# Sheet1.net
KiCad netlist of a schematic drawn in Altium Designer
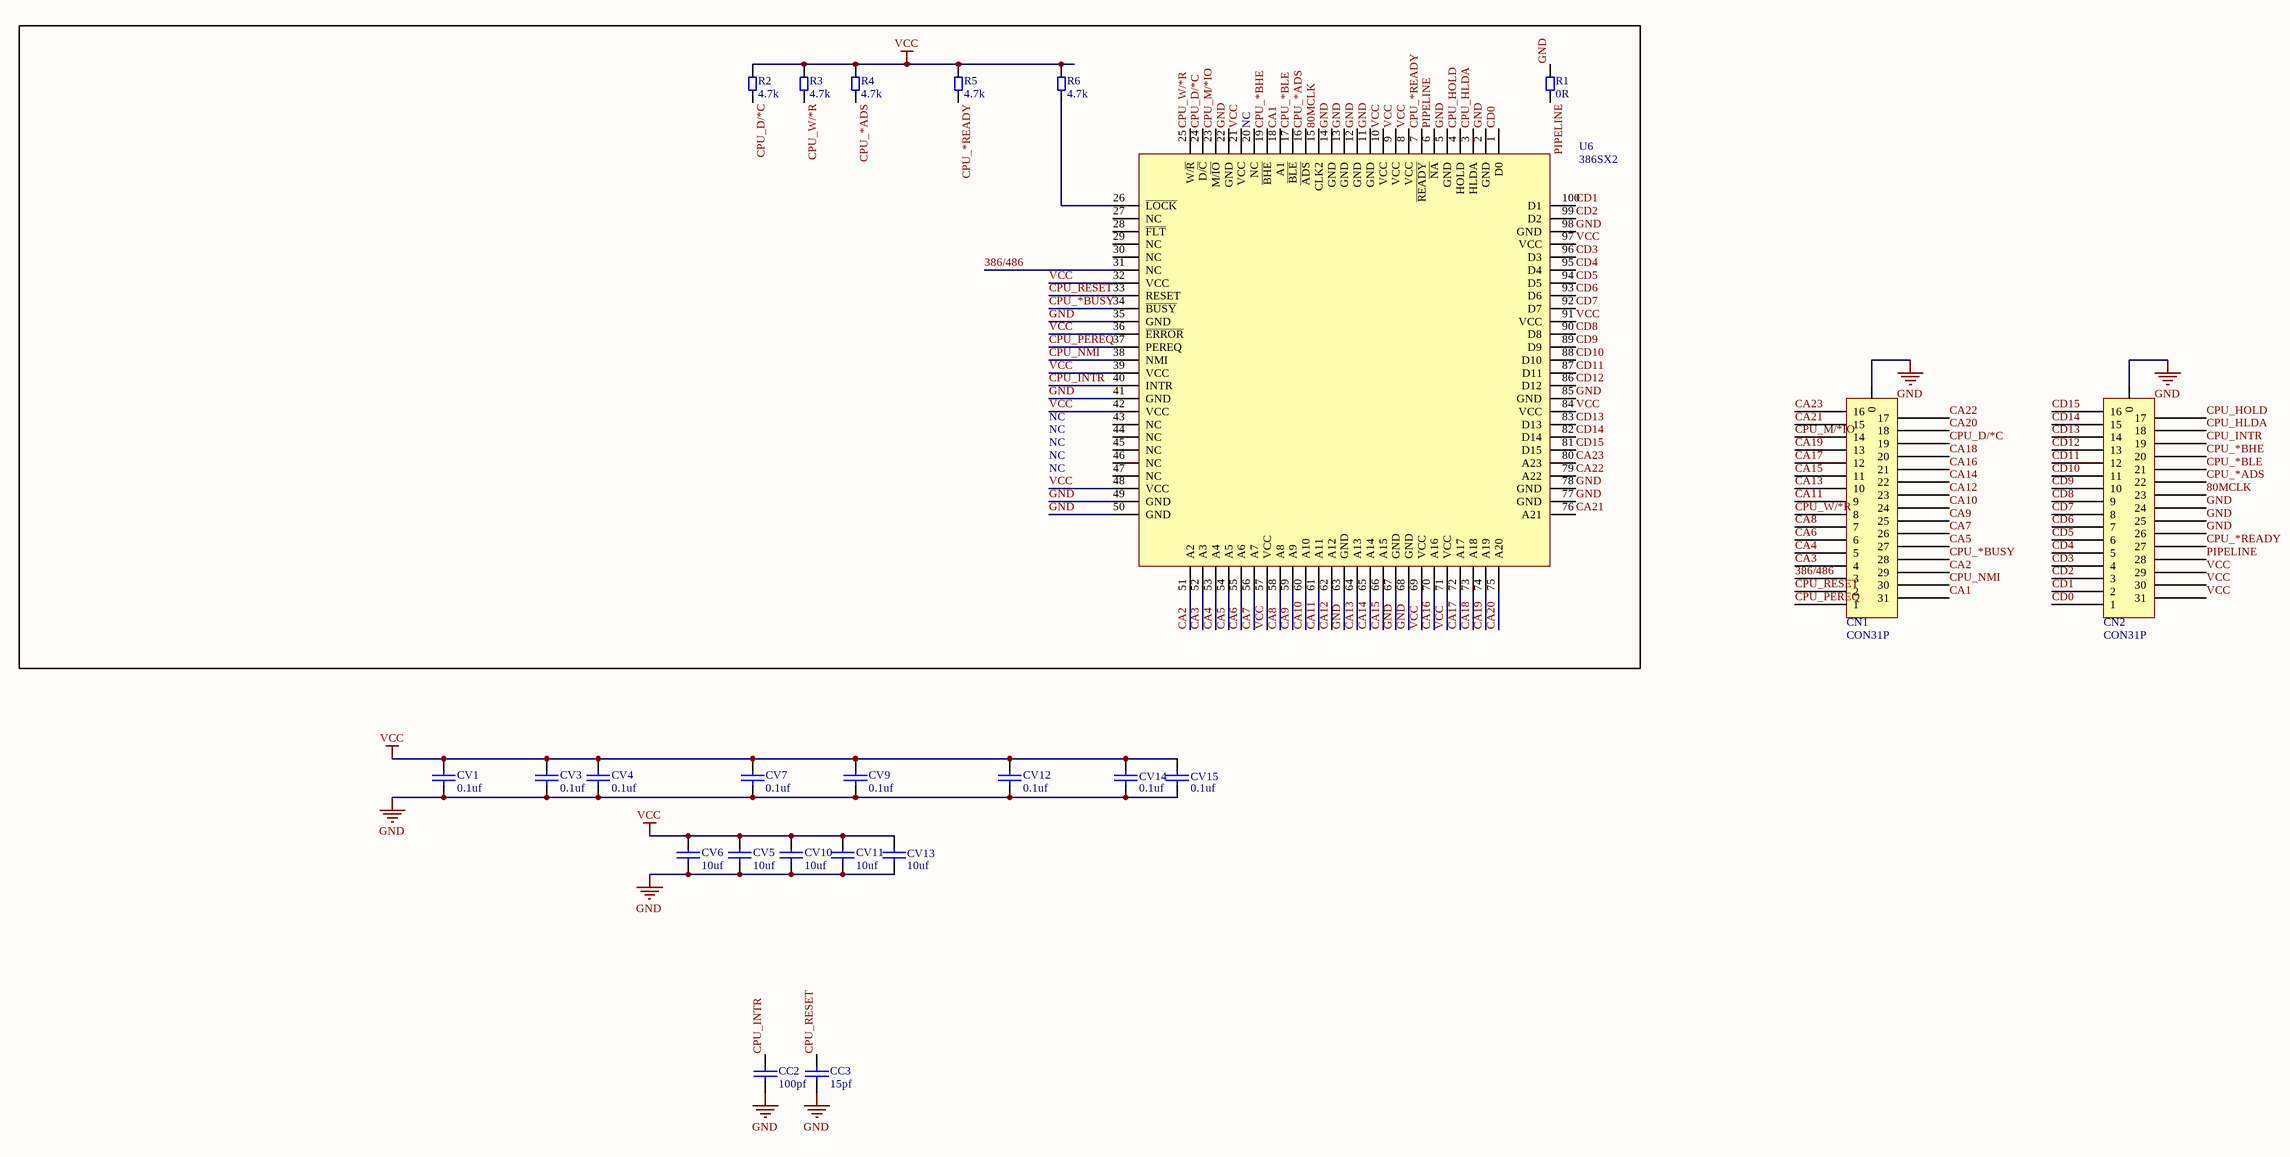
[diagram p0: Sheet1.SchDoc]

(export (version "E")
  (design (tool "Eeschema 10.0.6"))
  (components
    (comp (ref "CC2") (value "100pf") (footprint "C0603") (libsource (lib "电阻电容二极管") (part "CAP")))
    (comp (ref "CC3") (value "15pf") (footprint "C0603") (libsource (lib "电阻电容二极管") (part "CAP")))
    (comp (ref "CN1") (value "CON31P") (footprint "BTB1.0-31P-B") (libsource (lib "常用元件库") (part "CON31P")))
    (comp (ref "CN2") (value "CON31P") (footprint "BTB1.0-31P-B") (libsource (lib "常用元件库") (part "CON31P")))
    (comp (ref "CV1") (value "0.1uf") (footprint "C0603") (libsource (lib "电阻电容二极管") (part "CAP")))
    (comp (ref "CV3") (value "0.1uf") (footprint "C0603") (libsource (lib "电阻电容二极管") (part "CAP")))
    (comp (ref "CV4") (value "0.1uf") (footprint "C0603") (libsource (lib "电阻电容二极管") (part "CAP")))
    (comp (ref "CV5") (value "10uf") (footprint "C0603") (libsource (lib "电阻电容二极管") (part "CAP")))
    (comp (ref "CV6") (value "10uf") (footprint "C0603") (libsource (lib "电阻电容二极管") (part "CAP")))
    (comp (ref "CV7") (value "0.1uf") (footprint "C0603") (libsource (lib "电阻电容二极管") (part "CAP")))
    (comp (ref "CV9") (value "0.1uf") (footprint "C0603") (libsource (lib "电阻电容二极管") (part "CAP")))
    (comp (ref "CV10") (value "10uf") (footprint "C0603") (libsource (lib "电阻电容二极管") (part "CAP")))
    (comp (ref "CV11") (value "10uf") (footprint "C0603") (libsource (lib "电阻电容二极管") (part "CAP")))
    (comp (ref "CV12") (value "0.1uf") (footprint "C0603") (libsource (lib "电阻电容二极管") (part "CAP")))
    (comp (ref "CV13") (value "10uf") (footprint "C0603") (libsource (lib "电阻电容二极管") (part "CAP")))
    (comp (ref "CV14") (value "0.1uf") (footprint "C0603") (libsource (lib "电阻电容二极管") (part "CAP")))
    (comp (ref "CV15") (value "0.1uf") (footprint "C0603") (libsource (lib "电阻电容二极管") (part "CAP")))
    (comp (ref "R1") (value "0R") (footprint "R0603") (libsource (lib "电阻电容二极管") (part "RES2")))
    (comp (ref "R2") (value "4.7k") (footprint "R0603") (libsource (lib "电阻电容二极管") (part "RES2")))
    (comp (ref "R3") (value "4.7k") (footprint "R0603") (libsource (lib "电阻电容二极管") (part "RES2")))
    (comp (ref "R4") (value "4.7k") (footprint "R0603") (libsource (lib "电阻电容二极管") (part "RES2")))
    (comp (ref "R5") (value "4.7k") (footprint "R0603") (libsource (lib "电阻电容二极管") (part "RES2")))
    (comp (ref "R6") (value "4.7k") (footprint "R0603") (libsource (lib "电阻电容二极管") (part "RES2")))
    (comp (ref "U6") (value "386SX2") (footprint "PQFP100A") (libsource (lib "微机原理") (part "386SX2")))
  )
  (nets
    (net (code "1") (name "/80MCLK") (class "Default")
      (node (ref "CN2") (pin "23") (pinfunction "23_23") (pintype "passive"))
      (node (ref "U6") (pin "15") (pinfunction "CLK2_15") (pintype "passive"))
    )
    (net (code "2") (name "/386{slash}486") (class "Default")
      (node (ref "CN1") (pin "3") (pinfunction "3_3") (pintype "passive"))
      (node (ref "U6") (pin "31") (pinfunction "NC_31") (pintype "passive"))
    )
    (net (code "3") (name "/CA1") (class "Default")
      (node (ref "CN1") (pin "31") (pinfunction "31_31") (pintype "passive"))
      (node (ref "U6") (pin "18") (pinfunction "A1_18") (pintype "passive"))
    )
    (net (code "4") (name "/CA2") (class "Default")
      (node (ref "CN1") (pin "29") (pinfunction "29_29") (pintype "passive"))
      (node (ref "U6") (pin "51") (pinfunction "A2_51") (pintype "passive"))
    )
    (net (code "5") (name "/CA3") (class "Default")
      (node (ref "CN1") (pin "4") (pinfunction "4_4") (pintype "passive"))
      (node (ref "U6") (pin "52") (pinfunction "A3_52") (pintype "passive"))
    )
    (net (code "6") (name "/CA4") (class "Default")
      (node (ref "CN1") (pin "5") (pinfunction "5_5") (pintype "passive"))
      (node (ref "U6") (pin "53") (pinfunction "A4_53") (pintype "passive"))
    )
    (net (code "7") (name "/CA5") (class "Default")
      (node (ref "CN1") (pin "27") (pinfunction "27_27") (pintype "passive"))
      (node (ref "U6") (pin "54") (pinfunction "A5_54") (pintype "passive"))
    )
    (net (code "8") (name "/CA6") (class "Default")
      (node (ref "CN1") (pin "6") (pinfunction "6_6") (pintype "passive"))
      (node (ref "U6") (pin "55") (pinfunction "A6_55") (pintype "passive"))
    )
    (net (code "9") (name "/CA7") (class "Default")
      (node (ref "CN1") (pin "26") (pinfunction "26_26") (pintype "passive"))
      (node (ref "U6") (pin "56") (pinfunction "A7_56") (pintype "passive"))
    )
    (net (code "10") (name "/CA8") (class "Default")
      (node (ref "CN1") (pin "7") (pinfunction "7_7") (pintype "passive"))
      (node (ref "U6") (pin "58") (pinfunction "A8_58") (pintype "passive"))
    )
    (net (code "11") (name "/CA9") (class "Default")
      (node (ref "CN1") (pin "25") (pinfunction "25_25") (pintype "passive"))
      (node (ref "U6") (pin "59") (pinfunction "A9_59") (pintype "passive"))
    )
    (net (code "12") (name "/CA10") (class "Default")
      (node (ref "CN1") (pin "24") (pinfunction "24_24") (pintype "passive"))
      (node (ref "U6") (pin "60") (pinfunction "A10_60") (pintype "passive"))
    )
    (net (code "13") (name "/CA11") (class "Default")
      (node (ref "CN1") (pin "9") (pinfunction "9_9") (pintype "passive"))
      (node (ref "U6") (pin "61") (pinfunction "A11_61") (pintype "passive"))
    )
    (net (code "14") (name "/CA12") (class "Default")
      (node (ref "CN1") (pin "23") (pinfunction "23_23") (pintype "passive"))
      (node (ref "U6") (pin "62") (pinfunction "A12_62") (pintype "passive"))
    )
    (net (code "15") (name "/CA13") (class "Default")
      (node (ref "CN1") (pin "10") (pinfunction "10_10") (pintype "passive"))
      (node (ref "U6") (pin "64") (pinfunction "A13_64") (pintype "passive"))
    )
    (net (code "16") (name "/CA14") (class "Default")
      (node (ref "CN1") (pin "22") (pinfunction "22_22") (pintype "passive"))
      (node (ref "U6") (pin "65") (pinfunction "A14_65") (pintype "passive"))
    )
    (net (code "17") (name "/CA15") (class "Default")
      (node (ref "CN1") (pin "11") (pinfunction "11_11") (pintype "passive"))
      (node (ref "U6") (pin "66") (pinfunction "A15_66") (pintype "passive"))
    )
    (net (code "18") (name "/CA16") (class "Default")
      (node (ref "CN1") (pin "21") (pinfunction "21_21") (pintype "passive"))
      (node (ref "U6") (pin "70") (pinfunction "A16_70") (pintype "passive"))
    )
    (net (code "19") (name "/CA17") (class "Default")
      (node (ref "CN1") (pin "12") (pinfunction "12_12") (pintype "passive"))
      (node (ref "U6") (pin "72") (pinfunction "A17_72") (pintype "passive"))
    )
    (net (code "20") (name "/CA18") (class "Default")
      (node (ref "CN1") (pin "20") (pinfunction "20_20") (pintype "passive"))
      (node (ref "U6") (pin "73") (pinfunction "A18_73") (pintype "passive"))
    )
    (net (code "21") (name "/CA19") (class "Default")
      (node (ref "CN1") (pin "13") (pinfunction "13_13") (pintype "passive"))
      (node (ref "U6") (pin "74") (pinfunction "A19_74") (pintype "passive"))
    )
    (net (code "22") (name "/CA20") (class "Default")
      (node (ref "CN1") (pin "18") (pinfunction "18_18") (pintype "passive"))
      (node (ref "U6") (pin "75") (pinfunction "A20_75") (pintype "passive"))
    )
    (net (code "23") (name "/CA21") (class "Default")
      (node (ref "CN1") (pin "15") (pinfunction "15_15") (pintype "passive"))
      (node (ref "U6") (pin "76") (pinfunction "A21_76") (pintype "passive"))
    )
    (net (code "24") (name "/CA22") (class "Default")
      (node (ref "CN1") (pin "17") (pinfunction "17_17") (pintype "passive"))
      (node (ref "U6") (pin "79") (pinfunction "A22_79") (pintype "passive"))
    )
    (net (code "25") (name "/CA23") (class "Default")
      (node (ref "CN1") (pin "16") (pinfunction "16_16") (pintype "passive"))
      (node (ref "U6") (pin "80") (pinfunction "A23_80") (pintype "passive"))
    )
    (net (code "26") (name "/CD0") (class "Default")
      (node (ref "CN2") (pin "1") (pinfunction "1_1") (pintype "passive"))
      (node (ref "U6") (pin "1") (pinfunction "D0_1") (pintype "passive"))
    )
    (net (code "27") (name "/CD1") (class "Default")
      (node (ref "CN2") (pin "2") (pinfunction "2_2") (pintype "passive"))
      (node (ref "U6") (pin "100") (pinfunction "D1_100") (pintype "passive"))
    )
    (net (code "28") (name "/CD2") (class "Default")
      (node (ref "CN2") (pin "3") (pinfunction "3_3") (pintype "passive"))
      (node (ref "U6") (pin "99") (pinfunction "D2_99") (pintype "passive"))
    )
    (net (code "29") (name "/CD3") (class "Default")
      (node (ref "CN2") (pin "4") (pinfunction "4_4") (pintype "passive"))
      (node (ref "U6") (pin "96") (pinfunction "D3_96") (pintype "passive"))
    )
    (net (code "30") (name "/CD4") (class "Default")
      (node (ref "CN2") (pin "5") (pinfunction "5_5") (pintype "passive"))
      (node (ref "U6") (pin "95") (pinfunction "D4_95") (pintype "passive"))
    )
    (net (code "31") (name "/CD5") (class "Default")
      (node (ref "CN2") (pin "6") (pinfunction "6_6") (pintype "passive"))
      (node (ref "U6") (pin "94") (pinfunction "D5_94") (pintype "passive"))
    )
    (net (code "32") (name "/CD6") (class "Default")
      (node (ref "CN2") (pin "7") (pinfunction "7_7") (pintype "passive"))
      (node (ref "U6") (pin "93") (pinfunction "D6_93") (pintype "passive"))
    )
    (net (code "33") (name "/CD7") (class "Default")
      (node (ref "CN2") (pin "8") (pinfunction "8_8") (pintype "passive"))
      (node (ref "U6") (pin "92") (pinfunction "D7_92") (pintype "passive"))
    )
    (net (code "34") (name "/CD8") (class "Default")
      (node (ref "CN2") (pin "9") (pinfunction "9_9") (pintype "passive"))
      (node (ref "U6") (pin "90") (pinfunction "D8_90") (pintype "passive"))
    )
    (net (code "35") (name "/CD9") (class "Default")
      (node (ref "CN2") (pin "10") (pinfunction "10_10") (pintype "passive"))
      (node (ref "U6") (pin "89") (pinfunction "D9_89") (pintype "passive"))
    )
    (net (code "36") (name "/CD10") (class "Default")
      (node (ref "CN2") (pin "11") (pinfunction "11_11") (pintype "passive"))
      (node (ref "U6") (pin "88") (pinfunction "D10_88") (pintype "passive"))
    )
    (net (code "37") (name "/CD11") (class "Default")
      (node (ref "CN2") (pin "12") (pinfunction "12_12") (pintype "passive"))
      (node (ref "U6") (pin "87") (pinfunction "D11_87") (pintype "passive"))
    )
    (net (code "38") (name "/CD12") (class "Default")
      (node (ref "CN2") (pin "13") (pinfunction "13_13") (pintype "passive"))
      (node (ref "U6") (pin "86") (pinfunction "D12_86") (pintype "passive"))
    )
    (net (code "39") (name "/CD13") (class "Default")
      (node (ref "CN2") (pin "14") (pinfunction "14_14") (pintype "passive"))
      (node (ref "U6") (pin "83") (pinfunction "D13_83") (pintype "passive"))
    )
    (net (code "40") (name "/CD14") (class "Default")
      (node (ref "CN2") (pin "15") (pinfunction "15_15") (pintype "passive"))
      (node (ref "U6") (pin "82") (pinfunction "D14_82") (pintype "passive"))
    )
    (net (code "41") (name "/CD15") (class "Default")
      (node (ref "CN2") (pin "16") (pinfunction "16_16") (pintype "passive"))
      (node (ref "U6") (pin "81") (pinfunction "D15_81") (pintype "passive"))
    )
    (net (code "42") (name "/CPU_*ADS") (class "Default")
      (node (ref "CN2") (pin "22") (pinfunction "22_22") (pintype "passive"))
      (node (ref "R4") (pin "1") (pinfunction "1_1") (pintype "passive"))
      (node (ref "U6") (pin "16") (pinfunction "~{ADS}_16") (pintype "passive"))
    )
    (net (code "43") (name "/CPU_*BHE") (class "Default")
      (node (ref "CN2") (pin "20") (pinfunction "20_20") (pintype "passive"))
      (node (ref "U6") (pin "19") (pinfunction "~{BHE}_19") (pintype "passive"))
    )
    (net (code "44") (name "/CPU_*BLE") (class "Default")
      (node (ref "CN2") (pin "21") (pinfunction "21_21") (pintype "passive"))
      (node (ref "U6") (pin "17") (pinfunction "~{BLE}_17") (pintype "passive"))
    )
    (net (code "45") (name "/CPU_*BUSY") (class "Default")
      (node (ref "CN1") (pin "28") (pinfunction "28_28") (pintype "passive"))
      (node (ref "U6") (pin "34") (pinfunction "~{BUSY}_34") (pintype "passive"))
    )
    (net (code "46") (name "/CPU_*READY") (class "Default")
      (node (ref "CN2") (pin "27") (pinfunction "27_27") (pintype "passive"))
      (node (ref "R5") (pin "1") (pinfunction "1_1") (pintype "passive"))
      (node (ref "U6") (pin "7") (pinfunction "~{READY}_7") (pintype "passive"))
    )
    (net (code "47") (name "/CPU_D{slash}*C") (class "Default")
      (node (ref "CN1") (pin "19") (pinfunction "19_19") (pintype "passive"))
      (node (ref "R2") (pin "1") (pinfunction "1_1") (pintype "passive"))
      (node (ref "U6") (pin "24") (pinfunction "D/~{C}_24") (pintype "passive"))
    )
    (net (code "48") (name "/CPU_HLDA") (class "Default")
      (node (ref "CN2") (pin "18") (pinfunction "18_18") (pintype "passive"))
      (node (ref "U6") (pin "3") (pinfunction "HLDA_3") (pintype "passive"))
    )
    (net (code "49") (name "/CPU_HOLD") (class "Default")
      (node (ref "CN2") (pin "17") (pinfunction "17_17") (pintype "passive"))
      (node (ref "U6") (pin "4") (pinfunction "HOLD_4") (pintype "passive"))
    )
    (net (code "50") (name "/CPU_INTR") (class "Default")
      (node (ref "CC2") (pin "1") (pinfunction "1_1") (pintype "passive"))
      (node (ref "CN2") (pin "19") (pinfunction "19_19") (pintype "passive"))
      (node (ref "U6") (pin "40") (pinfunction "INTR_40") (pintype "passive"))
    )
    (net (code "51") (name "/CPU_M{slash}*IO") (class "Default")
      (node (ref "CN1") (pin "14") (pinfunction "14_14") (pintype "passive"))
      (node (ref "U6") (pin "23") (pinfunction "M/~{IO}_23") (pintype "passive"))
    )
    (net (code "52") (name "/CPU_NMI") (class "Default")
      (node (ref "CN1") (pin "30") (pinfunction "30_30") (pintype "passive"))
      (node (ref "U6") (pin "38") (pinfunction "NMI_38") (pintype "passive"))
    )
    (net (code "53") (name "/CPU_PEREQ") (class "Default")
      (node (ref "CN1") (pin "1") (pinfunction "1_1") (pintype "passive"))
      (node (ref "U6") (pin "37") (pinfunction "PEREQ_37") (pintype "passive"))
    )
    (net (code "54") (name "/CPU_RESET") (class "Default")
      (node (ref "CC3") (pin "1") (pinfunction "1_1") (pintype "passive"))
      (node (ref "CN1") (pin "2") (pinfunction "2_2") (pintype "passive"))
      (node (ref "U6") (pin "33") (pinfunction "RESET_33") (pintype "passive"))
    )
    (net (code "55") (name "/CPU_W{slash}*R") (class "Default")
      (node (ref "CN1") (pin "8") (pinfunction "8_8") (pintype "passive"))
      (node (ref "R3") (pin "1") (pinfunction "1_1") (pintype "passive"))
      (node (ref "U6") (pin "25") (pinfunction "W/~{R}_25") (pintype "passive"))
    )
    (net (code "56") (name "/PIPELINE") (class "Default")
      (node (ref "CN2") (pin "28") (pinfunction "28_28") (pintype "passive"))
      (node (ref "R1") (pin "1") (pinfunction "1_1") (pintype "passive"))
      (node (ref "U6") (pin "6") (pinfunction "~{NA}_6") (pintype "passive"))
    )
    (net (code "57") (name "GND") (class "Default")
      (node (ref "CC2") (pin "2") (pinfunction "2_2") (pintype "passive"))
      (node (ref "CC3") (pin "2") (pinfunction "2_2") (pintype "passive"))
      (node (ref "CN1") (pin "0") (pinfunction "0_0") (pintype "passive"))
      (node (ref "CN2") (pin "0") (pinfunction "0_0") (pintype "passive"))
      (node (ref "CN2") (pin "24") (pinfunction "24_24") (pintype "passive"))
      (node (ref "CN2") (pin "25") (pinfunction "25_25") (pintype "passive"))
      (node (ref "CN2") (pin "26") (pinfunction "26_26") (pintype "passive"))
      (node (ref "CV1") (pin "2") (pinfunction "2_2") (pintype "passive"))
      (node (ref "CV10") (pin "2") (pinfunction "2_2") (pintype "passive"))
      (node (ref "CV11") (pin "2") (pinfunction "2_2") (pintype "passive"))
      (node (ref "CV12") (pin "2") (pinfunction "2_2") (pintype "passive"))
      (node (ref "CV13") (pin "2") (pinfunction "2_2") (pintype "passive"))
      (node (ref "CV14") (pin "2") (pinfunction "2_2") (pintype "passive"))
      (node (ref "CV15") (pin "2") (pinfunction "2_2") (pintype "passive"))
      (node (ref "CV3") (pin "2") (pinfunction "2_2") (pintype "passive"))
      (node (ref "CV4") (pin "2") (pinfunction "2_2") (pintype "passive"))
      (node (ref "CV5") (pin "2") (pinfunction "2_2") (pintype "passive"))
      (node (ref "CV6") (pin "2") (pinfunction "2_2") (pintype "passive"))
      (node (ref "CV7") (pin "2") (pinfunction "2_2") (pintype "passive"))
      (node (ref "CV9") (pin "2") (pinfunction "2_2") (pintype "passive"))
      (node (ref "R1") (pin "2") (pinfunction "2_2") (pintype "passive"))
      (node (ref "U6") (pin "11") (pinfunction "GND_11") (pintype "passive"))
      (node (ref "U6") (pin "12") (pinfunction "GND_12") (pintype "passive"))
      (node (ref "U6") (pin "13") (pinfunction "GND_13") (pintype "passive"))
      (node (ref "U6") (pin "14") (pinfunction "GND_14") (pintype "passive"))
      (node (ref "U6") (pin "2") (pinfunction "GND_2") (pintype "passive"))
      (node (ref "U6") (pin "22") (pinfunction "GND_22") (pintype "passive"))
      (node (ref "U6") (pin "35") (pinfunction "GND_35") (pintype "passive"))
      (node (ref "U6") (pin "41") (pinfunction "GND_41") (pintype "passive"))
      (node (ref "U6") (pin "49") (pinfunction "GND_49") (pintype "passive"))
      (node (ref "U6") (pin "5") (pinfunction "GND_5") (pintype "passive"))
      (node (ref "U6") (pin "50") (pinfunction "GND_50") (pintype "passive"))
      (node (ref "U6") (pin "63") (pinfunction "GND_63") (pintype "passive"))
      (node (ref "U6") (pin "67") (pinfunction "GND_67") (pintype "passive"))
      (node (ref "U6") (pin "68") (pinfunction "GND_68") (pintype "passive"))
      (node (ref "U6") (pin "77") (pinfunction "GND_77") (pintype "passive"))
      (node (ref "U6") (pin "78") (pinfunction "GND_78") (pintype "passive"))
      (node (ref "U6") (pin "85") (pinfunction "GND_85") (pintype "passive"))
      (node (ref "U6") (pin "98") (pinfunction "GND_98") (pintype "passive"))
    )
    (net (code "58") (name "Net-(U6-~{LOCK})") (class "Default")
      (node (ref "R6") (pin "1") (pinfunction "1_1") (pintype "passive"))
      (node (ref "U6") (pin "26") (pinfunction "~{LOCK}_26") (pintype "passive"))
    )
    (net (code "59") (name "VCC") (class "Default")
      (node (ref "CN2") (pin "29") (pinfunction "29_29") (pintype "passive"))
      (node (ref "CN2") (pin "30") (pinfunction "30_30") (pintype "passive"))
      (node (ref "CN2") (pin "31") (pinfunction "31_31") (pintype "passive"))
      (node (ref "CV1") (pin "1") (pinfunction "1_1") (pintype "passive"))
      (node (ref "CV10") (pin "1") (pinfunction "1_1") (pintype "passive"))
      (node (ref "CV11") (pin "1") (pinfunction "1_1") (pintype "passive"))
      (node (ref "CV12") (pin "1") (pinfunction "1_1") (pintype "passive"))
      (node (ref "CV13") (pin "1") (pinfunction "1_1") (pintype "passive"))
      (node (ref "CV14") (pin "1") (pinfunction "1_1") (pintype "passive"))
      (node (ref "CV15") (pin "1") (pinfunction "1_1") (pintype "passive"))
      (node (ref "CV3") (pin "1") (pinfunction "1_1") (pintype "passive"))
      (node (ref "CV4") (pin "1") (pinfunction "1_1") (pintype "passive"))
      (node (ref "CV5") (pin "1") (pinfunction "1_1") (pintype "passive"))
      (node (ref "CV6") (pin "1") (pinfunction "1_1") (pintype "passive"))
      (node (ref "CV7") (pin "1") (pinfunction "1_1") (pintype "passive"))
      (node (ref "CV9") (pin "1") (pinfunction "1_1") (pintype "passive"))
      (node (ref "R2") (pin "2") (pinfunction "2_2") (pintype "passive"))
      (node (ref "R3") (pin "2") (pinfunction "2_2") (pintype "passive"))
      (node (ref "R4") (pin "2") (pinfunction "2_2") (pintype "passive"))
      (node (ref "R5") (pin "2") (pinfunction "2_2") (pintype "passive"))
      (node (ref "R6") (pin "2") (pinfunction "2_2") (pintype "passive"))
      (node (ref "U6") (pin "10") (pinfunction "VCC_10") (pintype "passive"))
      (node (ref "U6") (pin "21") (pinfunction "VCC_21") (pintype "passive"))
      (node (ref "U6") (pin "32") (pinfunction "VCC_32") (pintype "passive"))
      (node (ref "U6") (pin "36") (pinfunction "~{ERROR}_36") (pintype "passive"))
      (node (ref "U6") (pin "39") (pinfunction "VCC_39") (pintype "passive"))
      (node (ref "U6") (pin "42") (pinfunction "VCC_42") (pintype "passive"))
      (node (ref "U6") (pin "48") (pinfunction "VCC_48") (pintype "passive"))
      (node (ref "U6") (pin "57") (pinfunction "VCC_57") (pintype "passive"))
      (node (ref "U6") (pin "69") (pinfunction "VCC_69") (pintype "passive"))
      (node (ref "U6") (pin "71") (pinfunction "VCC_71") (pintype "passive"))
      (node (ref "U6") (pin "8") (pinfunction "VCC_8") (pintype "passive"))
      (node (ref "U6") (pin "84") (pinfunction "VCC_84") (pintype "passive"))
      (node (ref "U6") (pin "9") (pinfunction "VCC_9") (pintype "passive"))
      (node (ref "U6") (pin "91") (pinfunction "VCC_91") (pintype "passive"))
      (node (ref "U6") (pin "97") (pinfunction "VCC_97") (pintype "passive"))
    )
    (net (code "60") (name "unconnected-(U6-NC-Pad20)") (class "Default")
      (node (ref "U6") (pin "20") (pinfunction "NC_20") (pintype "passive"))
    )
    (net (code "61") (name "unconnected-(U6-NC-Pad27)") (class "Default")
      (node (ref "U6") (pin "27") (pinfunction "NC_27") (pintype "passive"))
    )
    (net (code "62") (name "unconnected-(U6-NC-Pad29)") (class "Default")
      (node (ref "U6") (pin "29") (pinfunction "NC_29") (pintype "passive"))
    )
    (net (code "63") (name "unconnected-(U6-NC-Pad30)") (class "Default")
      (node (ref "U6") (pin "30") (pinfunction "NC_30") (pintype "passive"))
    )
    (net (code "64") (name "unconnected-(U6-NC-Pad43)") (class "Default")
      (node (ref "U6") (pin "43") (pinfunction "NC_43") (pintype "passive"))
    )
    (net (code "65") (name "unconnected-(U6-NC-Pad44)") (class "Default")
      (node (ref "U6") (pin "44") (pinfunction "NC_44") (pintype "passive"))
    )
    (net (code "66") (name "unconnected-(U6-NC-Pad45)") (class "Default")
      (node (ref "U6") (pin "45") (pinfunction "NC_45") (pintype "passive"))
    )
    (net (code "67") (name "unconnected-(U6-NC-Pad46)") (class "Default")
      (node (ref "U6") (pin "46") (pinfunction "NC_46") (pintype "passive"))
    )
    (net (code "68") (name "unconnected-(U6-NC-Pad47)") (class "Default")
      (node (ref "U6") (pin "47") (pinfunction "NC_47") (pintype "passive"))
    )
    (net (code "69") (name "unconnected-(U6-~{FLT}-Pad28)") (class "Default")
      (node (ref "U6") (pin "28") (pinfunction "~{FLT}_28") (pintype "passive"))
    )
  )
)
